# Rover-4_Power_Supply.net
KiCad netlist of a schematic drawn in EAGLE
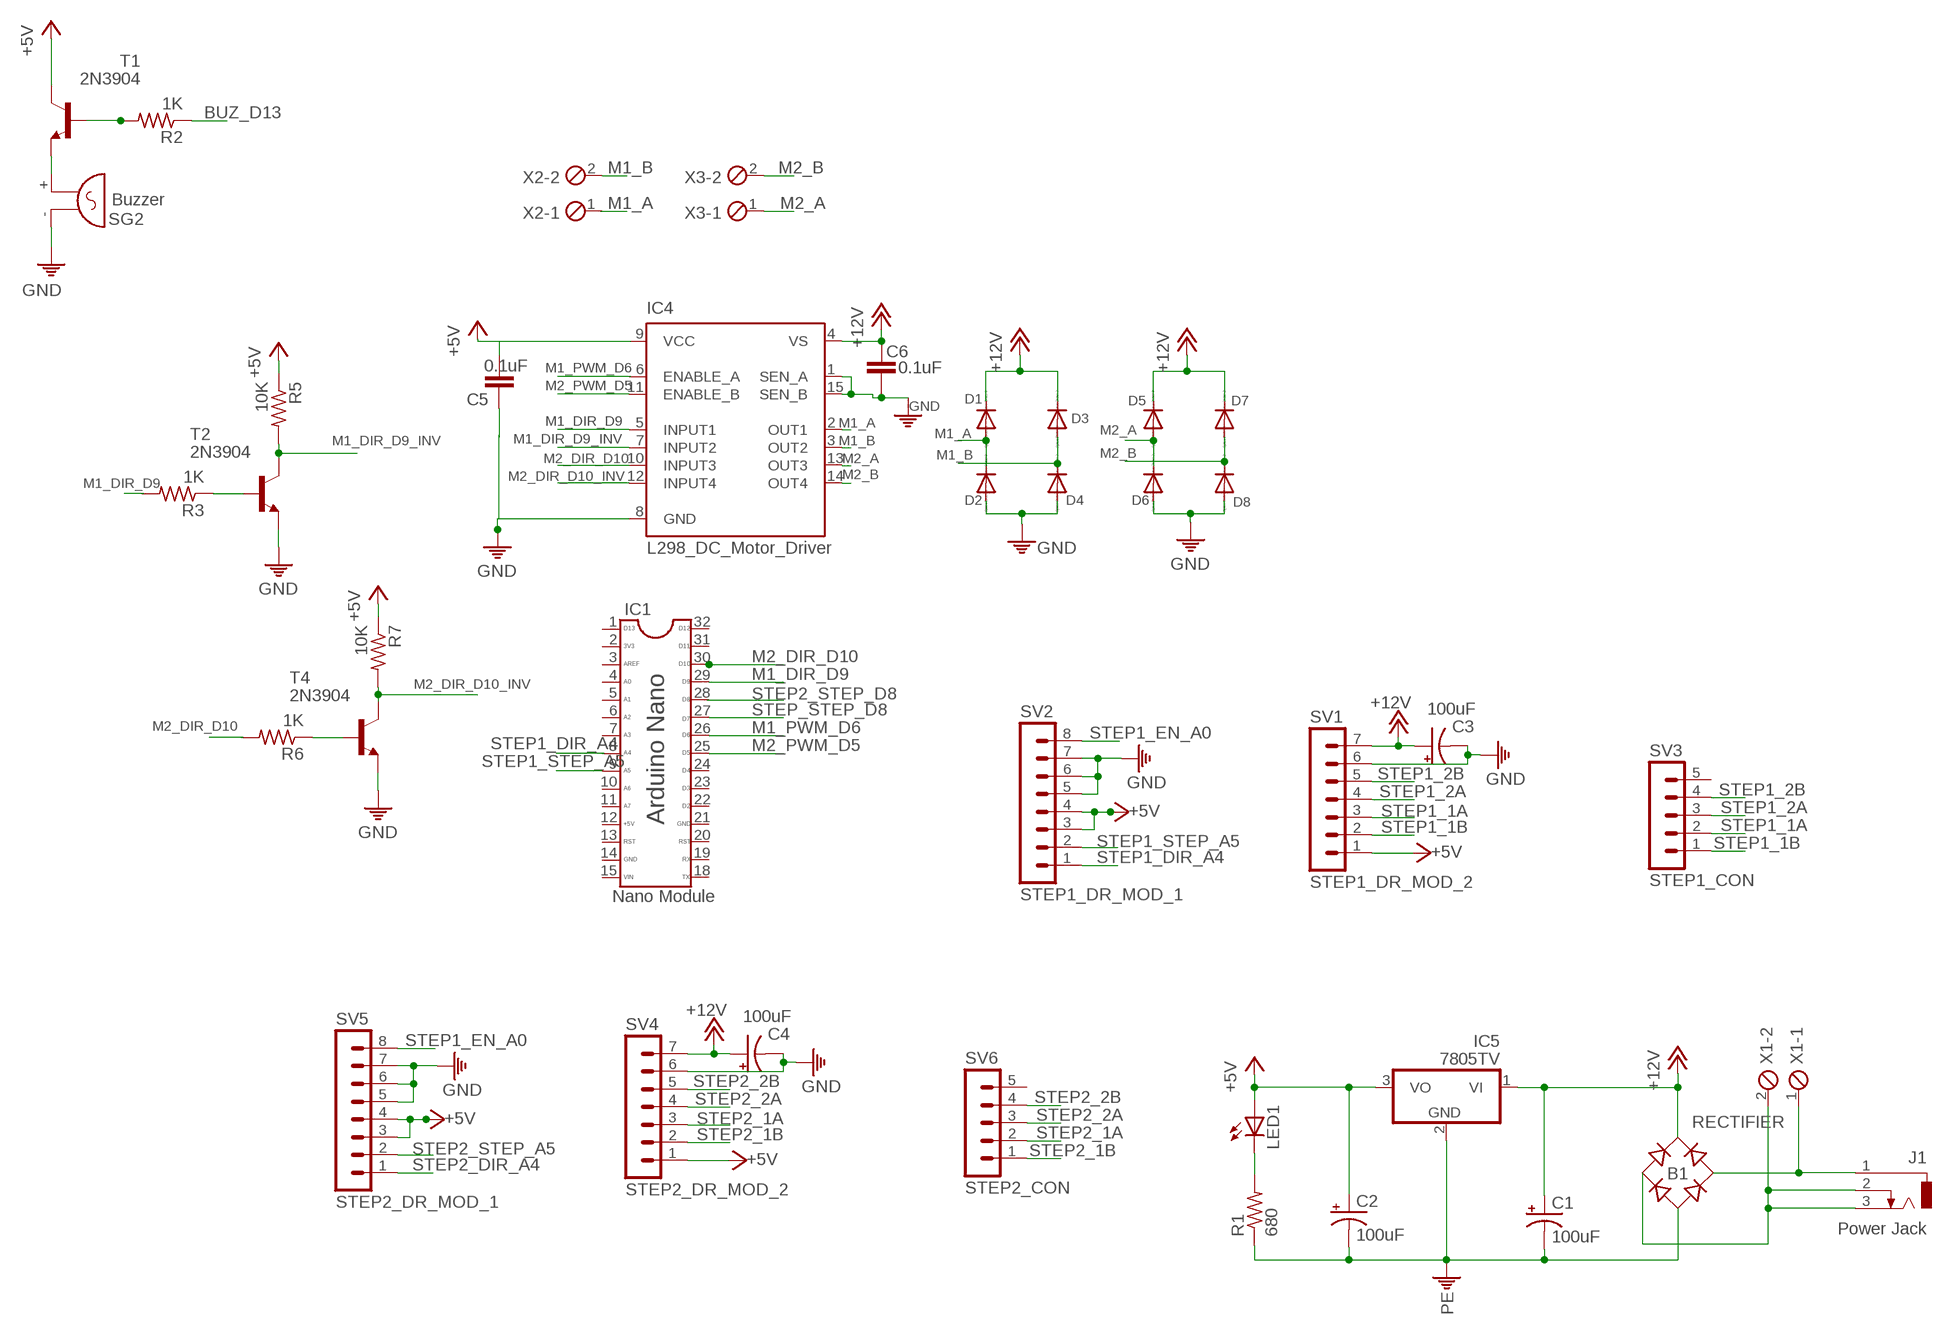
[diagram p0: schematic, sheet 1]

(export (version "E")
  (design (tool "Eeschema 10.0.6"))
  (components
    (comp (ref "B1")
      (value "RECTIFIER")
      (footprint "eagle-import:RB1A")
      (libsource (lib "eagle-import") (part "RB1A"))
    )
    (comp (ref "C1")
      (value "100uF")
      (footprint "eagle-import:E5-8,5")
      (libsource (lib "eagle-import") (part "CPOL-USE5-8.5"))
    )
    (comp (ref "C2")
      (value "100uF")
      (footprint "eagle-import:E5-8,5")
      (libsource (lib "eagle-import") (part "CPOL-USE5-8.5"))
    )
    (comp (ref "C3")
      (value "100uF")
      (footprint "eagle-import:E5-8,5")
      (libsource (lib "eagle-import") (part "CPOL-USE5-8.5"))
    )
    (comp (ref "C4")
      (value "100uF")
      (footprint "eagle-import:E5-8,5")
      (libsource (lib "eagle-import") (part "CPOL-USE5-8.5"))
    )
    (comp (ref "C5")
      (value "0.1uF")
      (footprint "eagle-import:C025-024X044")
      (libsource (lib "eagle-import") (part "C-EU025-024X044"))
    )
    (comp (ref "C6")
      (value "0.1uF")
      (footprint "eagle-import:C025-024X044")
      (libsource (lib "eagle-import") (part "C-EU025-024X044"))
    )
    (comp (ref "D1")
      (value "DIODE-D-2.5")
      (footprint "eagle-import:D-2.5")
      (libsource (lib "eagle-import") (part "DIODE-D-2.5"))
    )
    (comp (ref "D2")
      (value "DIODE-D-2.5")
      (footprint "eagle-import:D-2.5")
      (libsource (lib "eagle-import") (part "DIODE-D-2.5"))
    )
    (comp (ref "D3")
      (value "DIODE-D-2.5")
      (footprint "eagle-import:D-2.5")
      (libsource (lib "eagle-import") (part "DIODE-D-2.5"))
    )
    (comp (ref "D4")
      (value "DIODE-D-2.5")
      (footprint "eagle-import:D-2.5")
      (libsource (lib "eagle-import") (part "DIODE-D-2.5"))
    )
    (comp (ref "D5")
      (value "DIODE-D-2.5")
      (footprint "eagle-import:D-2.5")
      (libsource (lib "eagle-import") (part "DIODE-D-2.5"))
    )
    (comp (ref "D6")
      (value "DIODE-D-2.5")
      (footprint "eagle-import:D-2.5")
      (libsource (lib "eagle-import") (part "DIODE-D-2.5"))
    )
    (comp (ref "D7")
      (value "DIODE-D-2.5")
      (footprint "eagle-import:D-2.5")
      (libsource (lib "eagle-import") (part "DIODE-D-2.5"))
    )
    (comp (ref "D8")
      (value "DIODE-D-2.5")
      (footprint "eagle-import:D-2.5")
      (libsource (lib "eagle-import") (part "DIODE-D-2.5"))
    )
    (comp (ref "IC1")
      (value "Nano Module")
      (footprint "eagle-import:DIL32")
      (libsource (lib "eagle-import") (part "DIL32"))
    )
    (comp (ref "IC4")
      (value "L298_DC_Motor_Driver")
      (footprint "eagle-import:MULTIWATT-15")
      (fields (field (name "MPN") "L298N"))
      (libsource (lib "eagle-import") (part "L298"))
    )
    (comp (ref "IC5")
      (value "7805TV")
      (footprint "eagle-import:TO220V")
      (libsource (lib "eagle-import") (part "78TV05"))
    )
    (comp (ref "J1")
      (value "Power Jack")
      (footprint "eagle-import:ROVER-PW-JACL")
      (libsource (lib "eagle-import") (part "DCJ0303"))
    )
    (comp (ref "LED1")
      (value "LED3MM")
      (footprint "eagle-import:LED3MM")
      (libsource (lib "eagle-import") (part "LED3MM"))
    )
    (comp (ref "R1")
      (value "680")
      (footprint "eagle-import:0204_5")
      (libsource (lib "eagle-import") (part "R-US_0204/5"))
    )
    (comp (ref "R2")
      (value "1K")
      (footprint "eagle-import:0204_5")
      (libsource (lib "eagle-import") (part "R-US_0204/5"))
    )
    (comp (ref "R3")
      (value "1K")
      (footprint "eagle-import:0204_5")
      (libsource (lib "eagle-import") (part "R-US_0204/5"))
    )
    (comp (ref "R5")
      (value "10K")
      (footprint "eagle-import:0204_5")
      (libsource (lib "eagle-import") (part "R-US_0204/5"))
    )
    (comp (ref "R6")
      (value "1K")
      (footprint "eagle-import:0204_5")
      (libsource (lib "eagle-import") (part "R-US_0204/5"))
    )
    (comp (ref "R7")
      (value "10K")
      (footprint "eagle-import:0204_5")
      (libsource (lib "eagle-import") (part "R-US_0204/5"))
    )
    (comp (ref "SG2")
      (value "Buzzer")
      (footprint "eagle-import:F_QMX")
      (libsource (lib "eagle-import") (part "F/QMX"))
    )
    (comp (ref "SV1")
      (value "STEP1_DR_MOD_2")
      (footprint "eagle-import:MA07-1")
      (libsource (lib "eagle-import") (part "MA07-1"))
    )
    (comp (ref "SV2")
      (value "STEP1_DR_MOD_1")
      (footprint "eagle-import:MA08-1")
      (libsource (lib "eagle-import") (part "MA08-1"))
    )
    (comp (ref "SV3")
      (value "STEP1_CON")
      (footprint "eagle-import:MA05-1")
      (libsource (lib "eagle-import") (part "MA05-1"))
    )
    (comp (ref "SV4")
      (value "STEP2_DR_MOD_2")
      (footprint "eagle-import:MA07-1")
      (libsource (lib "eagle-import") (part "MA07-1"))
    )
    (comp (ref "SV5")
      (value "STEP2_DR_MOD_1")
      (footprint "eagle-import:MA08-1")
      (libsource (lib "eagle-import") (part "MA08-1"))
    )
    (comp (ref "SV6")
      (value "STEP2_CON")
      (footprint "eagle-import:MA05-1")
      (libsource (lib "eagle-import") (part "MA05-1"))
    )
    (comp (ref "T1")
      (value "2N3904")
      (footprint "eagle-import:TO92")
      (libsource (lib "eagle-import") (part "2N3904"))
    )
    (comp (ref "T2")
      (value "2N3904")
      (footprint "eagle-import:TO92")
      (libsource (lib "eagle-import") (part "2N3904"))
    )
    (comp (ref "T4")
      (value "2N3904")
      (footprint "eagle-import:TO92")
      (libsource (lib "eagle-import") (part "2N3904"))
    )
    (comp (ref "X1")
      (value "MPT2")
      (footprint "eagle-import:2POL254")
      (libsource (lib "eagle-import") (part "MPT2"))
    )
    (comp (ref "X2")
      (value "MPT2")
      (footprint "eagle-import:2POL254")
      (libsource (lib "eagle-import") (part "MPT2"))
    )
    (comp (ref "X3")
      (value "MPT2")
      (footprint "eagle-import:2POL254")
      (libsource (lib "eagle-import") (part "MPT2"))
    )
  )
  (nets
    (net (code "1") (name "+5V") (class "Default")
      (node (ref "C2") (pin "+") (pinfunction "+_+") (pintype "passive"))
      (node (ref "C5") (pin "2") (pinfunction "2_2") (pintype "passive"))
      (node (ref "IC5") (pin "3") (pinfunction "VO_3") (pintype "passive"))
      (node (ref "LED1") (pin "A") (pinfunction "A_A") (pintype "passive"))
      (node (ref "R5") (pin "1") (pinfunction "1_1") (pintype "passive"))
      (node (ref "R7") (pin "1") (pinfunction "1_1") (pintype "passive"))
      (node (ref "SV1") (pin "1") (pinfunction "1_1") (pintype "passive"))
      (node (ref "SV2") (pin "3") (pinfunction "3_3") (pintype "passive"))
      (node (ref "SV2") (pin "4") (pinfunction "4_4") (pintype "passive"))
      (node (ref "SV4") (pin "1") (pinfunction "1_1") (pintype "passive"))
      (node (ref "SV5") (pin "3") (pinfunction "3_3") (pintype "passive"))
      (node (ref "SV5") (pin "4") (pinfunction "4_4") (pintype "passive"))
      (node (ref "T1") (pin "1") (pinfunction "C_1") (pintype "passive"))
    )
    (net (code "2") (name "+12V") (class "Default")
      (node (ref "B1") (pin "+") (pinfunction "+_+") (pintype "passive"))
      (node (ref "C1") (pin "+") (pinfunction "+_+") (pintype "passive"))
      (node (ref "C3") (pin "+") (pinfunction "+_+") (pintype "passive"))
      (node (ref "C4") (pin "+") (pinfunction "+_+") (pintype "passive"))
      (node (ref "C6") (pin "2") (pinfunction "2_2") (pintype "passive"))
      (node (ref "D1") (pin "C") (pinfunction "C_C") (pintype "passive"))
      (node (ref "D3") (pin "C") (pinfunction "C_C") (pintype "passive"))
      (node (ref "D5") (pin "C") (pinfunction "C_C") (pintype "passive"))
      (node (ref "D7") (pin "C") (pinfunction "C_C") (pintype "passive"))
      (node (ref "IC4") (pin "4") (pinfunction "VS_4") (pintype "power_in"))
      (node (ref "IC5") (pin "1") (pinfunction "VI_1") (pintype "input"))
      (node (ref "SV1") (pin "7") (pinfunction "7_7") (pintype "passive"))
      (node (ref "SV4") (pin "7") (pinfunction "7_7") (pintype "passive"))
    )
    (net (code "3") (name "/BUZ_D13") (class "Default")
      (node (ref "R2") (pin "1") (pinfunction "1_1") (pintype "passive"))
    )
    (net (code "4") (name "/M1_A") (class "Default")
      (node (ref "D1") (pin "A") (pinfunction "A_A") (pintype "passive"))
      (node (ref "D2") (pin "C") (pinfunction "C_C") (pintype "passive"))
      (node (ref "IC4") (pin "2") (pinfunction "OUT1_2") (pintype "output"))
    )
    (net (code "5") (name "/M1_B") (class "Default")
      (node (ref "D3") (pin "A") (pinfunction "A_A") (pintype "passive"))
      (node (ref "D4") (pin "C") (pinfunction "C_C") (pintype "passive"))
      (node (ref "IC4") (pin "3") (pinfunction "OUT2_3") (pintype "output"))
      (node (ref "X2") (pin "2") (pinfunction "1_2") (pintype "passive"))
    )
    (net (code "6") (name "/M1_DIR_D9") (class "Default")
      (node (ref "IC1") (pin "29") (pinfunction "D9/PWM_29") (pintype "passive"))
      (node (ref "IC4") (pin "5") (pinfunction "INPUT1_5") (pintype "input"))
    )
    (net (code "7") (name "/M1_DIR_D9_INV") (class "Default")
      (node (ref "IC4") (pin "7") (pinfunction "INPUT2_7") (pintype "input"))
      (node (ref "R5") (pin "2") (pinfunction "2_2") (pintype "passive"))
      (node (ref "T2") (pin "1") (pinfunction "C_1") (pintype "passive"))
    )
    (net (code "8") (name "/M1_PWM_D6") (class "Default")
      (node (ref "IC1") (pin "26") (pinfunction "D6/PWM_26") (pintype "passive"))
    )
    (net (code "9") (name "/M2_A") (class "Default")
      (node (ref "D5") (pin "A") (pinfunction "A_A") (pintype "passive"))
      (node (ref "D6") (pin "C") (pinfunction "C_C") (pintype "passive"))
      (node (ref "IC4") (pin "13") (pinfunction "OUT3_13") (pintype "output"))
      (node (ref "X3") (pin "1") (pinfunction "1_1") (pintype "passive"))
    )
    (net (code "10") (name "/M2_B") (class "Default")
      (node (ref "D7") (pin "A") (pinfunction "A_A") (pintype "passive"))
      (node (ref "D8") (pin "C") (pinfunction "C_C") (pintype "passive"))
      (node (ref "IC4") (pin "14") (pinfunction "OUT4_14") (pintype "output"))
      (node (ref "X3") (pin "2") (pinfunction "1_2") (pintype "passive"))
    )
    (net (code "11") (name "/M2_DIR_D10") (class "Default")
      (node (ref "IC1") (pin "30") (pinfunction "D10/PWM_30") (pintype "passive"))
      (node (ref "IC4") (pin "10") (pinfunction "INPUT3_10") (pintype "input"))
    )
    (net (code "12") (name "/M2_DIR_D10_INV") (class "Default")
      (node (ref "IC4") (pin "12") (pinfunction "INPUT4_12") (pintype "input"))
      (node (ref "R7") (pin "2") (pinfunction "2_2") (pintype "passive"))
      (node (ref "T4") (pin "1") (pinfunction "C_1") (pintype "passive"))
    )
    (net (code "13") (name "/M2_PWM_D5") (class "Default")
      (node (ref "IC1") (pin "25") (pinfunction "D5/PWM_25") (pintype "passive"))
      (node (ref "IC4") (pin "11") (pinfunction "ENABLE_B_11") (pintype "input"))
    )
    (net (code "14") (name "/STEP1_1A") (class "Default")
      (node (ref "SV1") (pin "3") (pinfunction "3_3") (pintype "passive"))
      (node (ref "SV3") (pin "2") (pinfunction "2_2") (pintype "passive"))
    )
    (net (code "15") (name "/STEP1_1B") (class "Default")
      (node (ref "SV1") (pin "2") (pinfunction "2_2") (pintype "passive"))
      (node (ref "SV3") (pin "1") (pinfunction "1_1") (pintype "passive"))
    )
    (net (code "16") (name "/STEP1_2A") (class "Default")
      (node (ref "SV1") (pin "4") (pinfunction "4_4") (pintype "passive"))
      (node (ref "SV3") (pin "3") (pinfunction "3_3") (pintype "passive"))
    )
    (net (code "17") (name "/STEP1_2B") (class "Default")
      (node (ref "SV1") (pin "5") (pinfunction "5_5") (pintype "passive"))
      (node (ref "SV3") (pin "4") (pinfunction "4_4") (pintype "passive"))
    )
    (net (code "18") (name "/STEP1_DIR_A4") (class "Default")
      (node (ref "SV2") (pin "1") (pinfunction "1_1") (pintype "passive"))
    )
    (net (code "19") (name "/STEP1_EN_A0") (class "Default")
      (node (ref "SV2") (pin "8") (pinfunction "8_8") (pintype "passive"))
      (node (ref "SV5") (pin "8") (pinfunction "8_8") (pintype "passive"))
    )
    (net (code "20") (name "/STEP1_STEP_A5") (class "Default")
      (node (ref "IC1") (pin "9") (pinfunction "A5/D19/SCL_9") (pintype "passive"))
      (node (ref "SV2") (pin "2") (pinfunction "2_2") (pintype "passive"))
    )
    (net (code "21") (name "/STEP2_1A") (class "Default")
      (node (ref "SV4") (pin "3") (pinfunction "3_3") (pintype "passive"))
      (node (ref "SV6") (pin "2") (pinfunction "2_2") (pintype "passive"))
    )
    (net (code "22") (name "/STEP2_1B") (class "Default")
      (node (ref "SV4") (pin "2") (pinfunction "2_2") (pintype "passive"))
      (node (ref "SV6") (pin "1") (pinfunction "1_1") (pintype "passive"))
    )
    (net (code "23") (name "/STEP2_2A") (class "Default")
      (node (ref "SV4") (pin "4") (pinfunction "4_4") (pintype "passive"))
      (node (ref "SV6") (pin "3") (pinfunction "3_3") (pintype "passive"))
    )
    (net (code "24") (name "/STEP2_2B") (class "Default")
      (node (ref "SV4") (pin "5") (pinfunction "5_5") (pintype "passive"))
      (node (ref "SV6") (pin "4") (pinfunction "4_4") (pintype "passive"))
    )
    (net (code "25") (name "/STEP2_DIR_A4") (class "Default")
      (node (ref "SV5") (pin "1") (pinfunction "1_1") (pintype "passive"))
    )
    (net (code "26") (name "/STEP2_STEP_A5") (class "Default")
      (node (ref "SV5") (pin "2") (pinfunction "2_2") (pintype "passive"))
    )
    (net (code "28") (name "/STEP_STEP_D8") (class "Default")
      (node (ref "IC1") (pin "27") (pinfunction "D7_27") (pintype "passive"))
    )
    (net (code "29") (name "/VCC") (class "Default")
      (node (ref "IC4") (pin "9") (pinfunction "VCC_9") (pintype "power_in"))
    )
    (net (code "30") (name "GND") (class "Default")
      (node (ref "B1") (pin "-") (pinfunction "-_-") (pintype "passive"))
      (node (ref "C1") (pin "-") (pinfunction "-_-") (pintype "passive"))
      (node (ref "C2") (pin "-") (pinfunction "-_-") (pintype "passive"))
      (node (ref "C3") (pin "-") (pinfunction "-_-") (pintype "passive"))
      (node (ref "C4") (pin "-") (pinfunction "-_-") (pintype "passive"))
      (node (ref "C6") (pin "1") (pinfunction "1_1") (pintype "passive"))
      (node (ref "D2") (pin "A") (pinfunction "A_A") (pintype "passive"))
      (node (ref "D4") (pin "A") (pinfunction "A_A") (pintype "passive"))
      (node (ref "D6") (pin "A") (pinfunction "A_A") (pintype "passive"))
      (node (ref "D8") (pin "A") (pinfunction "A_A") (pintype "passive"))
      (node (ref "IC4") (pin "1") (pinfunction "SEN_A_1") (pintype "input"))
      (node (ref "IC4") (pin "15") (pinfunction "SEN_B_15") (pintype "input"))
      (node (ref "IC4") (pin "8") (pinfunction "GND_8") (pintype "power_in"))
      (node (ref "IC5") (pin "2") (pinfunction "GND_2") (pintype "passive"))
      (node (ref "R1") (pin "1") (pinfunction "1_1") (pintype "passive"))
      (node (ref "SG2") (pin "-") (pinfunction "1_-") (pintype "passive"))
      (node (ref "SV1") (pin "6") (pinfunction "6_6") (pintype "passive"))
      (node (ref "SV2") (pin "5") (pinfunction "5_5") (pintype "passive"))
      (node (ref "SV2") (pin "6") (pinfunction "6_6") (pintype "passive"))
      (node (ref "SV2") (pin "7") (pinfunction "7_7") (pintype "passive"))
      (node (ref "SV4") (pin "6") (pinfunction "6_6") (pintype "passive"))
      (node (ref "SV5") (pin "5") (pinfunction "5_5") (pintype "passive"))
      (node (ref "SV5") (pin "6") (pinfunction "6_6") (pintype "passive"))
      (node (ref "SV5") (pin "7") (pinfunction "7_7") (pintype "passive"))
      (node (ref "T2") (pin "3") (pinfunction "E_3") (pintype "passive"))
      (node (ref "T4") (pin "3") (pinfunction "E_3") (pintype "passive"))
    )
    (net (code "31") (name "Net-(B1-PadAC1)") (class "Default")
      (node (ref "B1") (pin "AC1") (pinfunction "AC1_AC1") (pintype "passive"))
      (node (ref "J1") (pin "1") (pinfunction "1_1") (pintype "passive"))
      (node (ref "X1") (pin "1") (pinfunction "1_1") (pintype "passive"))
    )
    (net (code "32") (name "Net-(LED1-C)") (class "Default")
      (node (ref "LED1") (pin "K") (pinfunction "C_K") (pintype "passive"))
      (node (ref "R1") (pin "2") (pinfunction "2_2") (pintype "passive"))
    )
    (net (code "33") (name "Net-(SG2-2)") (class "Default")
      (node (ref "SG2") (pin "+") (pinfunction "2_+") (pintype "passive"))
      (node (ref "T1") (pin "3") (pinfunction "E_3") (pintype "passive"))
    )
    (net (code "34") (name "Net-(T1-B)") (class "Default")
      (node (ref "R2") (pin "2") (pinfunction "2_2") (pintype "passive"))
      (node (ref "T1") (pin "2") (pinfunction "B_2") (pintype "passive"))
    )
    (net (code "35") (name "Net-(T2-B)") (class "Default")
      (node (ref "R3") (pin "1") (pinfunction "1_1") (pintype "passive"))
      (node (ref "T2") (pin "2") (pinfunction "B_2") (pintype "passive"))
    )
    (net (code "36") (name "Net-(T4-B)") (class "Default")
      (node (ref "R6") (pin "1") (pinfunction "1_1") (pintype "passive"))
      (node (ref "T4") (pin "2") (pinfunction "B_2") (pintype "passive"))
    )
    (net (code "37") (name "Net-(X1B-1)") (class "Default")
      (node (ref "B1") (pin "AC2") (pinfunction "AC2_AC2") (pintype "passive"))
      (node (ref "J1") (pin "2") (pinfunction "2_2") (pintype "passive"))
      (node (ref "J1") (pin "3") (pinfunction "3_3") (pintype "passive"))
      (node (ref "X1") (pin "2") (pinfunction "1_2") (pintype "passive"))
    )
    (net (code "38") (name "unconnected-(C5-Pad1)") (class "Default")
      (node (ref "C5") (pin "1") (pinfunction "1_1") (pintype "passive"))
    )
    (net (code "39") (name "unconnected-(IC1-3V3-Pad2)") (class "Default")
      (node (ref "IC1") (pin "2") (pinfunction "3V3_2") (pintype "passive"))
    )
    (net (code "40") (name "unconnected-(IC1-5V-Pad12)") (class "Default")
      (node (ref "IC1") (pin "12") (pinfunction "5V_12") (pintype "passive"))
    )
    (net (code "41") (name "unconnected-(IC1-A0{slash}D14-Pad4)") (class "Default")
      (node (ref "IC1") (pin "4") (pinfunction "A0/D14_4") (pintype "passive"))
    )
    (net (code "42") (name "unconnected-(IC1-A1{slash}D15-Pad5)") (class "Default")
      (node (ref "IC1") (pin "5") (pinfunction "A1/D15_5") (pintype "passive"))
    )
    (net (code "43") (name "unconnected-(IC1-A2{slash}D16-Pad6)") (class "Default")
      (node (ref "IC1") (pin "6") (pinfunction "A2/D16_6") (pintype "passive"))
    )
    (net (code "44") (name "unconnected-(IC1-A3{slash}D17-Pad7)") (class "Default")
      (node (ref "IC1") (pin "7") (pinfunction "A3/D17_7") (pintype "passive"))
    )
    (net (code "45") (name "unconnected-(IC1-A4{slash}D18{slash}SDA-Pad8)") (class "Default")
      (node (ref "IC1") (pin "8") (pinfunction "A4/D18/SDA_8") (pintype "passive"))
    )
    (net (code "46") (name "unconnected-(IC1-A6-Pad10)") (class "Default")
      (node (ref "IC1") (pin "10") (pinfunction "A6_10") (pintype "passive"))
    )
    (net (code "47") (name "unconnected-(IC1-A7-Pad11)") (class "Default")
      (node (ref "IC1") (pin "11") (pinfunction "A7_11") (pintype "passive"))
    )
    (net (code "48") (name "unconnected-(IC1-AREF-Pad3)") (class "Default")
      (node (ref "IC1") (pin "3") (pinfunction "AREF_3") (pintype "passive"))
    )
    (net (code "49") (name "unconnected-(IC1-D2-Pad22)") (class "Default")
      (node (ref "IC1") (pin "22") (pinfunction "D2_22") (pintype "passive"))
    )
    (net (code "50") (name "unconnected-(IC1-D3-Pad23)") (class "Default")
      (node (ref "IC1") (pin "23") (pinfunction "D3_23") (pintype "passive"))
    )
    (net (code "51") (name "unconnected-(IC1-D4-Pad24)") (class "Default")
      (node (ref "IC1") (pin "24") (pinfunction "D4_24") (pintype "passive"))
    )
    (net (code "52") (name "unconnected-(IC1-D8-Pad28)") (class "Default")
      (node (ref "IC1") (pin "28") (pinfunction "D8_28") (pintype "passive"))
    )
    (net (code "53") (name "unconnected-(IC1-D11{slash}MOSI-Pad31)") (class "Default")
      (node (ref "IC1") (pin "31") (pinfunction "D11/MOSI_31") (pintype "passive"))
    )
    (net (code "54") (name "unconnected-(IC1-D12{slash}MISO-Pad32)") (class "Default")
      (node (ref "IC1") (pin "32") (pinfunction "D12/MISO_32") (pintype "passive"))
    )
    (net (code "55") (name "unconnected-(IC1-D13-Pad1)") (class "Default")
      (node (ref "IC1") (pin "1") (pinfunction "D13_1") (pintype "passive"))
    )
    (net (code "56") (name "unconnected-(IC1-GND1-Pad14)") (class "Default")
      (node (ref "IC1") (pin "14") (pinfunction "GND1_14") (pintype "passive"))
    )
    (net (code "57") (name "unconnected-(IC1-GND2-Pad21)") (class "Default")
      (node (ref "IC1") (pin "21") (pinfunction "GND2_21") (pintype "passive"))
    )
    (net (code "58") (name "unconnected-(IC1-RST1-Pad13)") (class "Default")
      (node (ref "IC1") (pin "13") (pinfunction "RST1_13") (pintype "passive"))
    )
    (net (code "59") (name "unconnected-(IC1-RST2-Pad20)") (class "Default")
      (node (ref "IC1") (pin "20") (pinfunction "RST2_20") (pintype "passive"))
    )
    (net (code "60") (name "unconnected-(IC1-RX-Pad19)") (class "Default")
      (node (ref "IC1") (pin "19") (pinfunction "RX_19") (pintype "passive"))
    )
    (net (code "61") (name "unconnected-(IC1-TX-Pad18)") (class "Default")
      (node (ref "IC1") (pin "18") (pinfunction "TX_18") (pintype "passive"))
    )
    (net (code "62") (name "unconnected-(IC1-VIN-Pad15)") (class "Default")
      (node (ref "IC1") (pin "15") (pinfunction "VIN_15") (pintype "passive"))
    )
    (net (code "63") (name "unconnected-(IC4-ENABLE_A-Pad6)") (class "Default")
      (node (ref "IC4") (pin "6") (pinfunction "ENABLE_A_6") (pintype "input"))
    )
    (net (code "64") (name "unconnected-(R3-Pad2)") (class "Default")
      (node (ref "R3") (pin "2") (pinfunction "2_2") (pintype "passive"))
    )
    (net (code "65") (name "unconnected-(R6-Pad2)") (class "Default")
      (node (ref "R6") (pin "2") (pinfunction "2_2") (pintype "passive"))
    )
    (net (code "66") (name "unconnected-(SV3-Pad5)") (class "Default")
      (node (ref "SV3") (pin "5") (pinfunction "5_5") (pintype "passive"))
    )
    (net (code "67") (name "unconnected-(SV6-Pad5)") (class "Default")
      (node (ref "SV6") (pin "5") (pinfunction "5_5") (pintype "passive"))
    )
    (net (code "68") (name "unconnected-(X2-Pad1)") (class "Default")
      (node (ref "X2") (pin "1") (pinfunction "1_1") (pintype "passive"))
    )
  )
)
